# usir_board.net
KiCad netlist of a schematic drawn in EAGLE
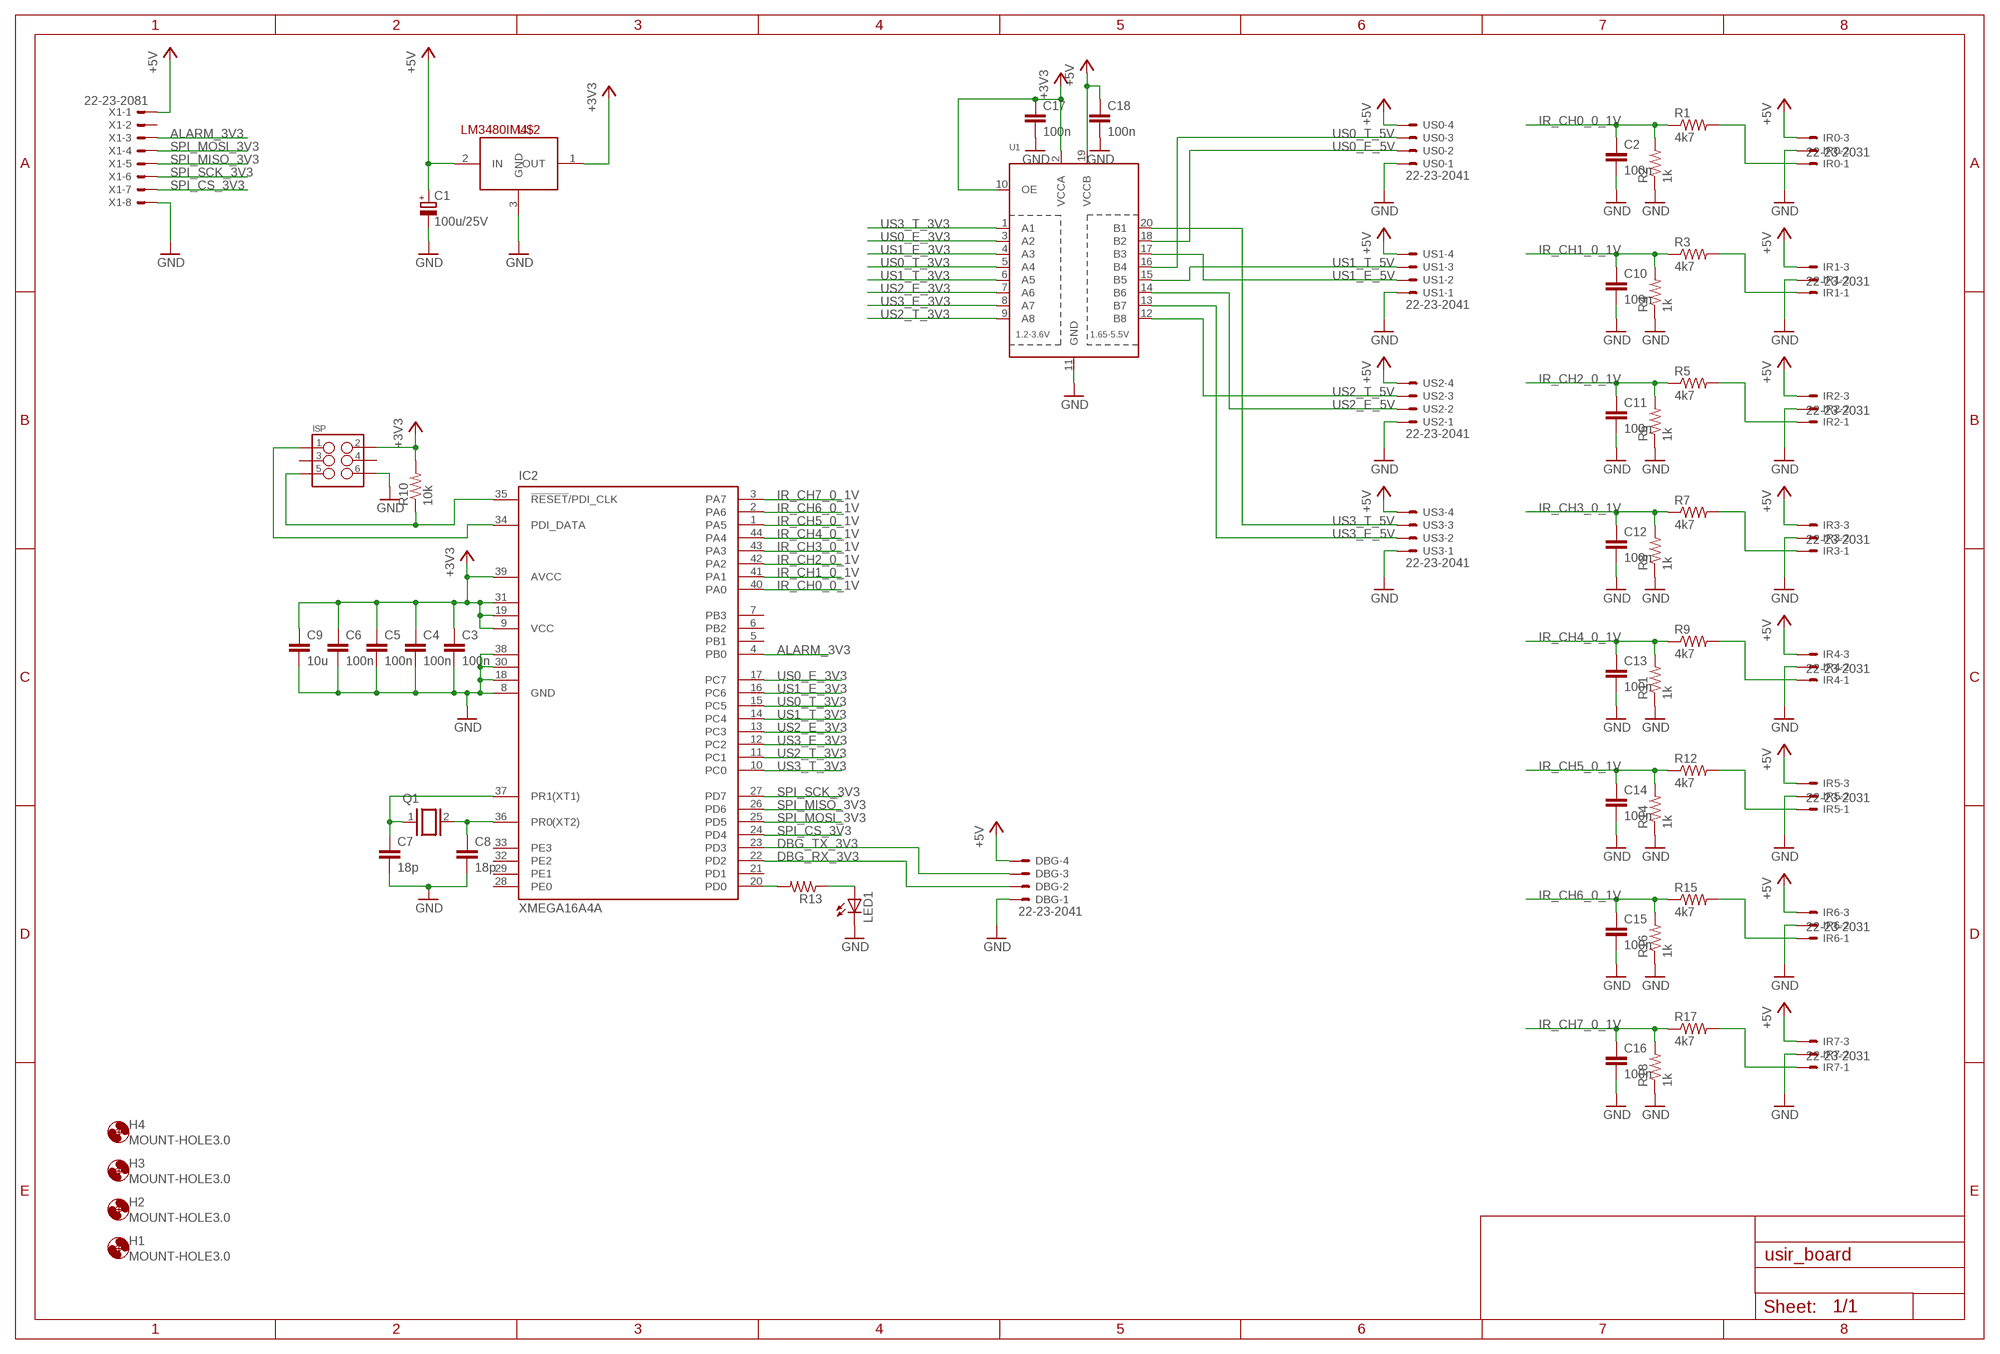
[diagram p0: schematic, sheet 1]

(export (version "E")
  (design (tool "Eeschema 10.0.6"))
  (components
    (comp (ref "C1")
      (value "100u/25V")
      (footprint "eagle-import:PANASONIC_E")
      (libsource (lib "eagle-import") (part "CPOL-EUE"))
    )
    (comp (ref "C2")
      (value "100n")
      (footprint "eagle-import:C0603")
      (libsource (lib "eagle-import") (part "C-EUC0603"))
    )
    (comp (ref "C3")
      (value "100n")
      (footprint "eagle-import:C0603")
      (libsource (lib "eagle-import") (part "C-EUC0603"))
    )
    (comp (ref "C4")
      (value "100n")
      (footprint "eagle-import:C0603")
      (libsource (lib "eagle-import") (part "C-EUC0603"))
    )
    (comp (ref "C5")
      (value "100n")
      (footprint "eagle-import:C0603")
      (libsource (lib "eagle-import") (part "C-EUC0603"))
    )
    (comp (ref "C6")
      (value "100n")
      (footprint "eagle-import:C0603")
      (libsource (lib "eagle-import") (part "C-EUC0603"))
    )
    (comp (ref "C7")
      (value "18p")
      (footprint "eagle-import:C0603")
      (libsource (lib "eagle-import") (part "C-EUC0603"))
    )
    (comp (ref "C8")
      (value "18p")
      (footprint "eagle-import:C0603")
      (libsource (lib "eagle-import") (part "C-EUC0603"))
    )
    (comp (ref "C9")
      (value "10u")
      (footprint "eagle-import:C0805")
      (libsource (lib "eagle-import") (part "C-EUC0805"))
    )
    (comp (ref "C10")
      (value "100n")
      (footprint "eagle-import:C0603")
      (libsource (lib "eagle-import") (part "C-EUC0603"))
    )
    (comp (ref "C11")
      (value "100n")
      (footprint "eagle-import:C0603")
      (libsource (lib "eagle-import") (part "C-EUC0603"))
    )
    (comp (ref "C12")
      (value "100n")
      (footprint "eagle-import:C0603")
      (libsource (lib "eagle-import") (part "C-EUC0603"))
    )
    (comp (ref "C13")
      (value "100n")
      (footprint "eagle-import:C0603")
      (libsource (lib "eagle-import") (part "C-EUC0603"))
    )
    (comp (ref "C14")
      (value "100n")
      (footprint "eagle-import:C0603")
      (libsource (lib "eagle-import") (part "C-EUC0603"))
    )
    (comp (ref "C15")
      (value "100n")
      (footprint "eagle-import:C0603")
      (libsource (lib "eagle-import") (part "C-EUC0603"))
    )
    (comp (ref "C16")
      (value "100n")
      (footprint "eagle-import:C0603")
      (libsource (lib "eagle-import") (part "C-EUC0603"))
    )
    (comp (ref "C17")
      (value "100n")
      (footprint "eagle-import:C0603")
      (libsource (lib "eagle-import") (part "C-EUC0603"))
    )
    (comp (ref "C18")
      (value "100n")
      (footprint "eagle-import:C0603")
      (libsource (lib "eagle-import") (part "C-EUC0603"))
    )
    (comp (ref "DBG")
      (value "22-23-2041")
      (footprint "eagle-import:22-23-2041")
      (fields (field (name "MF") "MOLEX"))
      (libsource (lib "eagle-import") (part "22-23-2041"))
    )
    (comp (ref "H1")
      (value "MOUNT-HOLE3.0")
      (footprint "eagle-import:3,0")
      (libsource (lib "eagle-import") (part "MOUNT-HOLE3.0"))
    )
    (comp (ref "H2")
      (value "MOUNT-HOLE3.0")
      (footprint "eagle-import:3,0")
      (libsource (lib "eagle-import") (part "MOUNT-HOLE3.0"))
    )
    (comp (ref "H3")
      (value "MOUNT-HOLE3.0")
      (footprint "eagle-import:3,0")
      (libsource (lib "eagle-import") (part "MOUNT-HOLE3.0"))
    )
    (comp (ref "H4")
      (value "MOUNT-HOLE3.0")
      (footprint "eagle-import:3,0")
      (libsource (lib "eagle-import") (part "MOUNT-HOLE3.0"))
    )
    (comp (ref "IC2")
      (value "XMEGA16A4A")
      (footprint "eagle-import:TQFP44")
      (libsource (lib "eagle-import") (part "XMEGA16A4A"))
    )
    (comp (ref "IR0")
      (value "22-23-2031")
      (footprint "eagle-import:22-23-2031")
      (fields (field (name "MF") "MOLEX"))
      (libsource (lib "eagle-import") (part "22-23-2031"))
    )
    (comp (ref "IR1")
      (value "22-23-2031")
      (footprint "eagle-import:22-23-2031")
      (fields (field (name "MF") "MOLEX"))
      (libsource (lib "eagle-import") (part "22-23-2031"))
    )
    (comp (ref "IR2")
      (value "22-23-2031")
      (footprint "eagle-import:22-23-2031")
      (fields (field (name "MF") "MOLEX"))
      (libsource (lib "eagle-import") (part "22-23-2031"))
    )
    (comp (ref "IR3")
      (value "22-23-2031")
      (footprint "eagle-import:22-23-2031")
      (fields (field (name "MF") "MOLEX"))
      (libsource (lib "eagle-import") (part "22-23-2031"))
    )
    (comp (ref "IR4")
      (value "22-23-2031")
      (footprint "eagle-import:22-23-2031")
      (fields (field (name "MF") "MOLEX"))
      (libsource (lib "eagle-import") (part "22-23-2031"))
    )
    (comp (ref "IR5")
      (value "22-23-2031")
      (footprint "eagle-import:22-23-2031")
      (fields (field (name "MF") "MOLEX"))
      (libsource (lib "eagle-import") (part "22-23-2031"))
    )
    (comp (ref "IR6")
      (value "22-23-2031")
      (footprint "eagle-import:22-23-2031")
      (fields (field (name "MF") "MOLEX"))
      (libsource (lib "eagle-import") (part "22-23-2031"))
    )
    (comp (ref "IR7")
      (value "22-23-2031")
      (footprint "eagle-import:22-23-2031")
      (fields (field (name "MF") "MOLEX"))
      (libsource (lib "eagle-import") (part "22-23-2031"))
    )
    (comp (ref "ISP")
      (value "M03X2POGO_PINS")
      (footprint "eagle-import:2X3_POGO")
      (libsource (lib "eagle-import") (part "M03X2POGO_PINS"))
    )
    (comp (ref "LED1")
      (value "LEDCHIP-LED0603")
      (footprint "eagle-import:CHIP-LED0603")
      (libsource (lib "eagle-import") (part "LEDCHIP-LED0603"))
    )
    (comp (ref "Q1")
      (value "XTAL/S")
      (footprint "eagle-import:QS")
      (libsource (lib "eagle-import") (part "XTAL/S"))
    )
    (comp (ref "R1")
      (value "4k7")
      (footprint "eagle-import:R0603")
      (libsource (lib "eagle-import") (part "R-US_R0603"))
    )
    (comp (ref "R2")
      (value "1k")
      (footprint "eagle-import:R0603")
      (libsource (lib "eagle-import") (part "R-US_R0603"))
    )
    (comp (ref "R3")
      (value "4k7")
      (footprint "eagle-import:R0603")
      (libsource (lib "eagle-import") (part "R-US_R0603"))
    )
    (comp (ref "R4")
      (value "1k")
      (footprint "eagle-import:R0603")
      (libsource (lib "eagle-import") (part "R-US_R0603"))
    )
    (comp (ref "R5")
      (value "4k7")
      (footprint "eagle-import:R0603")
      (libsource (lib "eagle-import") (part "R-US_R0603"))
    )
    (comp (ref "R6")
      (value "1k")
      (footprint "eagle-import:R0603")
      (libsource (lib "eagle-import") (part "R-US_R0603"))
    )
    (comp (ref "R7")
      (value "4k7")
      (footprint "eagle-import:R0603")
      (libsource (lib "eagle-import") (part "R-US_R0603"))
    )
    (comp (ref "R8")
      (value "1k")
      (footprint "eagle-import:R0603")
      (libsource (lib "eagle-import") (part "R-US_R0603"))
    )
    (comp (ref "R9")
      (value "4k7")
      (footprint "eagle-import:R0603")
      (libsource (lib "eagle-import") (part "R-US_R0603"))
    )
    (comp (ref "R10")
      (value "10k")
      (footprint "eagle-import:R0603")
      (libsource (lib "eagle-import") (part "R-US_R0603"))
    )
    (comp (ref "R11")
      (value "1k")
      (footprint "eagle-import:R0603")
      (libsource (lib "eagle-import") (part "R-US_R0603"))
    )
    (comp (ref "R12")
      (value "4k7")
      (footprint "eagle-import:R0603")
      (libsource (lib "eagle-import") (part "R-US_R0603"))
    )
    (comp (ref "R13")
      (value "R-US_R0603")
      (footprint "eagle-import:R0603")
      (libsource (lib "eagle-import") (part "R-US_R0603"))
    )
    (comp (ref "R14")
      (value "1k")
      (footprint "eagle-import:R0603")
      (libsource (lib "eagle-import") (part "R-US_R0603"))
    )
    (comp (ref "R15")
      (value "4k7")
      (footprint "eagle-import:R0603")
      (libsource (lib "eagle-import") (part "R-US_R0603"))
    )
    (comp (ref "R16")
      (value "1k")
      (footprint "eagle-import:R0603")
      (libsource (lib "eagle-import") (part "R-US_R0603"))
    )
    (comp (ref "R17")
      (value "4k7")
      (footprint "eagle-import:R0603")
      (libsource (lib "eagle-import") (part "R-US_R0603"))
    )
    (comp (ref "R18")
      (value "1k")
      (footprint "eagle-import:R0603")
      (libsource (lib "eagle-import") (part "R-US_R0603"))
    )
    (comp (ref "U$2")
      (value "LM3480IM4")
      (footprint "eagle-import:SOT23-3")
      (libsource (lib "eagle-import") (part "LM3480IM4"))
    )
    (comp (ref "U1")
      (value "TXB0108PWR")
      (footprint "eagle-import:TSSOP20")
      (libsource (lib "eagle-import") (part "TXB0108PWR"))
    )
    (comp (ref "US0")
      (value "22-23-2041")
      (footprint "eagle-import:22-23-2041")
      (fields (field (name "MF") "MOLEX"))
      (libsource (lib "eagle-import") (part "22-23-2041"))
    )
    (comp (ref "US1")
      (value "22-23-2041")
      (footprint "eagle-import:22-23-2041")
      (fields (field (name "MF") "MOLEX"))
      (libsource (lib "eagle-import") (part "22-23-2041"))
    )
    (comp (ref "US2")
      (value "22-23-2041")
      (footprint "eagle-import:22-23-2041")
      (fields (field (name "MF") "MOLEX"))
      (libsource (lib "eagle-import") (part "22-23-2041"))
    )
    (comp (ref "US3")
      (value "22-23-2041")
      (footprint "eagle-import:22-23-2041")
      (fields (field (name "MF") "MOLEX"))
      (libsource (lib "eagle-import") (part "22-23-2041"))
    )
    (comp (ref "X1")
      (value "22-23-2081")
      (footprint "eagle-import:22-23-2081")
      (fields (field (name "MF") "MOLEX"))
      (libsource (lib "eagle-import") (part "22-23-2081"))
    )
  )
  (nets
    (net (code "1") (name "+3V3") (class "Default")
      (node (ref "C17") (pin "1") (pinfunction "1_1") (pintype "passive"))
      (node (ref "C3") (pin "1") (pinfunction "1_1") (pintype "passive"))
      (node (ref "C4") (pin "1") (pinfunction "1_1") (pintype "passive"))
      (node (ref "C5") (pin "1") (pinfunction "1_1") (pintype "passive"))
      (node (ref "C6") (pin "1") (pinfunction "1_1") (pintype "passive"))
      (node (ref "C9") (pin "1") (pinfunction "1_1") (pintype "passive"))
      (node (ref "IC2") (pin "19") (pinfunction "VCC1_19") (pintype "power_in"))
      (node (ref "IC2") (pin "31") (pinfunction "VCC2_31") (pintype "power_in"))
      (node (ref "IC2") (pin "39") (pinfunction "AVCC_39") (pintype "power_in"))
      (node (ref "IC2") (pin "9") (pinfunction "VCC_9") (pintype "power_in"))
      (node (ref "ISP") (pin "P$2") (pinfunction "2_P$2") (pintype "bidirectional"))
      (node (ref "R10") (pin "2") (pinfunction "2_2") (pintype "passive"))
      (node (ref "U$2") (pin "1") (pinfunction "OUT_1") (pintype "bidirectional"))
      (node (ref "U1") (pin "10") (pinfunction "OE_10") (pintype "bidirectional"))
      (node (ref "U1") (pin "2") (pinfunction "VCCA_2") (pintype "bidirectional"))
    )
    (net (code "2") (name "+5V") (class "Default")
      (node (ref "C1") (pin "+") (pinfunction "+_+") (pintype "passive"))
      (node (ref "C18") (pin "1") (pinfunction "1_1") (pintype "passive"))
      (node (ref "DBG") (pin "4") (pinfunction "S_4") (pintype "passive"))
      (node (ref "IR0") (pin "3") (pinfunction "S_3") (pintype "passive"))
      (node (ref "IR1") (pin "3") (pinfunction "S_3") (pintype "passive"))
      (node (ref "IR2") (pin "3") (pinfunction "S_3") (pintype "passive"))
      (node (ref "IR3") (pin "3") (pinfunction "S_3") (pintype "passive"))
      (node (ref "IR4") (pin "3") (pinfunction "S_3") (pintype "passive"))
      (node (ref "IR5") (pin "3") (pinfunction "S_3") (pintype "passive"))
      (node (ref "IR6") (pin "3") (pinfunction "S_3") (pintype "passive"))
      (node (ref "IR7") (pin "3") (pinfunction "S_3") (pintype "passive"))
      (node (ref "U$2") (pin "2") (pinfunction "IN_2") (pintype "bidirectional"))
      (node (ref "U1") (pin "19") (pinfunction "VCCB_19") (pintype "bidirectional"))
      (node (ref "US0") (pin "4") (pinfunction "S_4") (pintype "passive"))
      (node (ref "US1") (pin "4") (pinfunction "S_4") (pintype "passive"))
      (node (ref "US2") (pin "4") (pinfunction "S_4") (pintype "passive"))
      (node (ref "US3") (pin "4") (pinfunction "S_4") (pintype "passive"))
      (node (ref "X1") (pin "1") (pinfunction "S_1") (pintype "passive"))
    )
    (net (code "3") (name "/ALARM_3V3") (class "Default")
      (node (ref "IC2") (pin "4") (pinfunction "PB0_4") (pintype "bidirectional"))
      (node (ref "X1") (pin "3") (pinfunction "S_3") (pintype "passive"))
    )
    (net (code "4") (name "/DBG_RX_3V3") (class "Default")
      (node (ref "DBG") (pin "2") (pinfunction "S_2") (pintype "passive"))
      (node (ref "IC2") (pin "22") (pinfunction "PD2_22") (pintype "bidirectional"))
    )
    (net (code "5") (name "/DBG_TX_3V3") (class "Default")
      (node (ref "DBG") (pin "3") (pinfunction "S_3") (pintype "passive"))
      (node (ref "IC2") (pin "23") (pinfunction "PD3_23") (pintype "bidirectional"))
    )
    (net (code "6") (name "/IR_CH0_0_1V") (class "Default")
      (node (ref "C2") (pin "1") (pinfunction "1_1") (pintype "passive"))
      (node (ref "IC2") (pin "40") (pinfunction "PA0_40") (pintype "bidirectional"))
      (node (ref "R1") (pin "1") (pinfunction "1_1") (pintype "passive"))
      (node (ref "R2") (pin "2") (pinfunction "2_2") (pintype "passive"))
    )
    (net (code "7") (name "/IR_CH1_0_1V") (class "Default")
      (node (ref "C10") (pin "1") (pinfunction "1_1") (pintype "passive"))
      (node (ref "IC2") (pin "41") (pinfunction "PA1_41") (pintype "bidirectional"))
      (node (ref "R3") (pin "1") (pinfunction "1_1") (pintype "passive"))
      (node (ref "R4") (pin "2") (pinfunction "2_2") (pintype "passive"))
    )
    (net (code "8") (name "/IR_CH2_0_1V") (class "Default")
      (node (ref "C11") (pin "1") (pinfunction "1_1") (pintype "passive"))
      (node (ref "IC2") (pin "42") (pinfunction "PA2_42") (pintype "bidirectional"))
      (node (ref "R5") (pin "1") (pinfunction "1_1") (pintype "passive"))
      (node (ref "R6") (pin "2") (pinfunction "2_2") (pintype "passive"))
    )
    (net (code "9") (name "/IR_CH3_0_1V") (class "Default")
      (node (ref "C12") (pin "1") (pinfunction "1_1") (pintype "passive"))
      (node (ref "IC2") (pin "43") (pinfunction "PA3_43") (pintype "bidirectional"))
      (node (ref "R7") (pin "1") (pinfunction "1_1") (pintype "passive"))
      (node (ref "R8") (pin "2") (pinfunction "2_2") (pintype "passive"))
    )
    (net (code "10") (name "/IR_CH4_0_1V") (class "Default")
      (node (ref "C13") (pin "1") (pinfunction "1_1") (pintype "passive"))
      (node (ref "IC2") (pin "44") (pinfunction "PA4_44") (pintype "bidirectional"))
      (node (ref "R11") (pin "2") (pinfunction "2_2") (pintype "passive"))
      (node (ref "R9") (pin "1") (pinfunction "1_1") (pintype "passive"))
    )
    (net (code "11") (name "/IR_CH5_0_1V") (class "Default")
      (node (ref "C14") (pin "1") (pinfunction "1_1") (pintype "passive"))
      (node (ref "IC2") (pin "1") (pinfunction "PA5_1") (pintype "bidirectional"))
      (node (ref "R12") (pin "1") (pinfunction "1_1") (pintype "passive"))
      (node (ref "R14") (pin "2") (pinfunction "2_2") (pintype "passive"))
    )
    (net (code "12") (name "/IR_CH6_0_1V") (class "Default")
      (node (ref "C15") (pin "1") (pinfunction "1_1") (pintype "passive"))
      (node (ref "IC2") (pin "2") (pinfunction "PA6_2") (pintype "bidirectional"))
      (node (ref "R15") (pin "1") (pinfunction "1_1") (pintype "passive"))
      (node (ref "R16") (pin "2") (pinfunction "2_2") (pintype "passive"))
    )
    (net (code "13") (name "/IR_CH7_0_1V") (class "Default")
      (node (ref "C16") (pin "1") (pinfunction "1_1") (pintype "passive"))
      (node (ref "IC2") (pin "3") (pinfunction "PA7_3") (pintype "bidirectional"))
      (node (ref "R17") (pin "1") (pinfunction "1_1") (pintype "passive"))
      (node (ref "R18") (pin "2") (pinfunction "2_2") (pintype "passive"))
    )
    (net (code "14") (name "/SPI_CS_3V3") (class "Default")
      (node (ref "IC2") (pin "24") (pinfunction "PD4_24") (pintype "bidirectional"))
      (node (ref "X1") (pin "7") (pinfunction "S_7") (pintype "passive"))
    )
    (net (code "15") (name "/SPI_MISO_3V3") (class "Default")
      (node (ref "IC2") (pin "26") (pinfunction "PD6_26") (pintype "bidirectional"))
      (node (ref "X1") (pin "5") (pinfunction "S_5") (pintype "passive"))
    )
    (net (code "16") (name "/SPI_MOSI_3V3") (class "Default")
      (node (ref "IC2") (pin "25") (pinfunction "PD5_25") (pintype "bidirectional"))
      (node (ref "X1") (pin "4") (pinfunction "S_4") (pintype "passive"))
    )
    (net (code "17") (name "/SPI_SCK_3V3") (class "Default")
      (node (ref "IC2") (pin "27") (pinfunction "PD7_27") (pintype "bidirectional"))
      (node (ref "X1") (pin "6") (pinfunction "S_6") (pintype "passive"))
    )
    (net (code "18") (name "/US0_E_3V3") (class "Default")
      (node (ref "IC2") (pin "17") (pinfunction "PC7_17") (pintype "bidirectional"))
      (node (ref "U1") (pin "3") (pinfunction "A2_3") (pintype "bidirectional"))
    )
    (net (code "19") (name "/US0_E_5V") (class "Default")
      (node (ref "U1") (pin "18") (pinfunction "B2_18") (pintype "bidirectional"))
      (node (ref "US0") (pin "2") (pinfunction "S_2") (pintype "passive"))
    )
    (net (code "20") (name "/US0_T_3V3") (class "Default")
      (node (ref "IC2") (pin "15") (pinfunction "PC5_15") (pintype "bidirectional"))
      (node (ref "U1") (pin "5") (pinfunction "A4_5") (pintype "bidirectional"))
    )
    (net (code "21") (name "/US0_T_5V") (class "Default")
      (node (ref "U1") (pin "16") (pinfunction "B4_16") (pintype "bidirectional"))
      (node (ref "US0") (pin "3") (pinfunction "S_3") (pintype "passive"))
    )
    (net (code "22") (name "/US1_E_3V3") (class "Default")
      (node (ref "IC2") (pin "16") (pinfunction "PC6_16") (pintype "bidirectional"))
      (node (ref "U1") (pin "4") (pinfunction "A3_4") (pintype "bidirectional"))
    )
    (net (code "23") (name "/US1_E_5V") (class "Default")
      (node (ref "U1") (pin "17") (pinfunction "B3_17") (pintype "bidirectional"))
      (node (ref "US1") (pin "2") (pinfunction "S_2") (pintype "passive"))
    )
    (net (code "24") (name "/US1_T_3V3") (class "Default")
      (node (ref "IC2") (pin "14") (pinfunction "PC4_14") (pintype "bidirectional"))
      (node (ref "U1") (pin "6") (pinfunction "A5_6") (pintype "bidirectional"))
    )
    (net (code "25") (name "/US1_T_5V") (class "Default")
      (node (ref "U1") (pin "15") (pinfunction "B5_15") (pintype "bidirectional"))
      (node (ref "US1") (pin "3") (pinfunction "S_3") (pintype "passive"))
    )
    (net (code "26") (name "/US2_E_3V3") (class "Default")
      (node (ref "IC2") (pin "13") (pinfunction "PC3_13") (pintype "bidirectional"))
      (node (ref "U1") (pin "7") (pinfunction "A6_7") (pintype "bidirectional"))
    )
    (net (code "27") (name "/US2_E_5V") (class "Default")
      (node (ref "U1") (pin "14") (pinfunction "B6_14") (pintype "bidirectional"))
      (node (ref "US2") (pin "2") (pinfunction "S_2") (pintype "passive"))
    )
    (net (code "28") (name "/US2_T_3V3") (class "Default")
      (node (ref "IC2") (pin "11") (pinfunction "PC1_11") (pintype "bidirectional"))
      (node (ref "U1") (pin "9") (pinfunction "A8_9") (pintype "bidirectional"))
    )
    (net (code "29") (name "/US2_T_5V") (class "Default")
      (node (ref "U1") (pin "12") (pinfunction "B8_12") (pintype "bidirectional"))
      (node (ref "US2") (pin "3") (pinfunction "S_3") (pintype "passive"))
    )
    (net (code "30") (name "/US3_E_3V3") (class "Default")
      (node (ref "IC2") (pin "12") (pinfunction "PC2_12") (pintype "bidirectional"))
      (node (ref "U1") (pin "8") (pinfunction "A7_8") (pintype "bidirectional"))
    )
    (net (code "31") (name "/US3_E_5V") (class "Default")
      (node (ref "U1") (pin "13") (pinfunction "B7_13") (pintype "bidirectional"))
      (node (ref "US3") (pin "2") (pinfunction "S_2") (pintype "passive"))
    )
    (net (code "32") (name "/US3_T_3V3") (class "Default")
      (node (ref "IC2") (pin "10") (pinfunction "PC0_10") (pintype "bidirectional"))
      (node (ref "U1") (pin "1") (pinfunction "A1_1") (pintype "bidirectional"))
    )
    (net (code "33") (name "/US3_T_5V") (class "Default")
      (node (ref "U1") (pin "20") (pinfunction "B1_20") (pintype "bidirectional"))
      (node (ref "US3") (pin "3") (pinfunction "S_3") (pintype "passive"))
    )
    (net (code "34") (name "GND") (class "Default")
      (node (ref "C1") (pin "-") (pinfunction "-_-") (pintype "passive"))
      (node (ref "C10") (pin "2") (pinfunction "2_2") (pintype "passive"))
      (node (ref "C11") (pin "2") (pinfunction "2_2") (pintype "passive"))
      (node (ref "C12") (pin "2") (pinfunction "2_2") (pintype "passive"))
      (node (ref "C13") (pin "2") (pinfunction "2_2") (pintype "passive"))
      (node (ref "C14") (pin "2") (pinfunction "2_2") (pintype "passive"))
      (node (ref "C15") (pin "2") (pinfunction "2_2") (pintype "passive"))
      (node (ref "C16") (pin "2") (pinfunction "2_2") (pintype "passive"))
      (node (ref "C17") (pin "2") (pinfunction "2_2") (pintype "passive"))
      (node (ref "C18") (pin "2") (pinfunction "2_2") (pintype "passive"))
      (node (ref "C2") (pin "2") (pinfunction "2_2") (pintype "passive"))
      (node (ref "C3") (pin "2") (pinfunction "2_2") (pintype "passive"))
      (node (ref "C4") (pin "2") (pinfunction "2_2") (pintype "passive"))
      (node (ref "C5") (pin "2") (pinfunction "2_2") (pintype "passive"))
      (node (ref "C6") (pin "2") (pinfunction "2_2") (pintype "passive"))
      (node (ref "C7") (pin "2") (pinfunction "2_2") (pintype "passive"))
      (node (ref "C8") (pin "2") (pinfunction "2_2") (pintype "passive"))
      (node (ref "C9") (pin "2") (pinfunction "2_2") (pintype "passive"))
      (node (ref "DBG") (pin "1") (pinfunction "S_1") (pintype "passive"))
      (node (ref "IC2") (pin "18") (pinfunction "GND1_18") (pintype "power_in"))
      (node (ref "IC2") (pin "30") (pinfunction "GND2_30") (pintype "power_in"))
      (node (ref "IC2") (pin "38") (pinfunction "GND3_38") (pintype "power_in"))
      (node (ref "IC2") (pin "8") (pinfunction "GND_8") (pintype "power_in"))
      (node (ref "IR0") (pin "2") (pinfunction "S_2") (pintype "passive"))
      (node (ref "IR1") (pin "2") (pinfunction "S_2") (pintype "passive"))
      (node (ref "IR2") (pin "2") (pinfunction "S_2") (pintype "passive"))
      (node (ref "IR3") (pin "2") (pinfunction "S_2") (pintype "passive"))
      (node (ref "IR4") (pin "2") (pinfunction "S_2") (pintype "passive"))
      (node (ref "IR5") (pin "2") (pinfunction "S_2") (pintype "passive"))
      (node (ref "IR6") (pin "2") (pinfunction "S_2") (pintype "passive"))
      (node (ref "IR7") (pin "2") (pinfunction "S_2") (pintype "passive"))
      (node (ref "ISP") (pin "P$6") (pinfunction "6_P$6") (pintype "bidirectional"))
      (node (ref "LED1") (pin "C") (pinfunction "C_C") (pintype "passive"))
      (node (ref "R11") (pin "1") (pinfunction "1_1") (pintype "passive"))
      (node (ref "R14") (pin "1") (pinfunction "1_1") (pintype "passive"))
      (node (ref "R16") (pin "1") (pinfunction "1_1") (pintype "passive"))
      (node (ref "R18") (pin "1") (pinfunction "1_1") (pintype "passive"))
      (node (ref "R2") (pin "1") (pinfunction "1_1") (pintype "passive"))
      (node (ref "R4") (pin "1") (pinfunction "1_1") (pintype "passive"))
      (node (ref "R6") (pin "1") (pinfunction "1_1") (pintype "passive"))
      (node (ref "R8") (pin "1") (pinfunction "1_1") (pintype "passive"))
      (node (ref "U$2") (pin "3") (pinfunction "GND_3") (pintype "bidirectional"))
      (node (ref "U1") (pin "11") (pinfunction "GND_11") (pintype "bidirectional"))
      (node (ref "US0") (pin "1") (pinfunction "S_1") (pintype "passive"))
      (node (ref "US1") (pin "1") (pinfunction "S_1") (pintype "passive"))
      (node (ref "US2") (pin "1") (pinfunction "S_1") (pintype "passive"))
      (node (ref "US3") (pin "1") (pinfunction "S_1") (pintype "passive"))
      (node (ref "X1") (pin "8") (pinfunction "S_8") (pintype "passive"))
    )
    (net (code "35") (name "Net-(IC2-PD0)") (class "Default")
      (node (ref "IC2") (pin "20") (pinfunction "PD0_20") (pintype "bidirectional"))
      (node (ref "R13") (pin "2") (pinfunction "2_2") (pintype "passive"))
    )
    (net (code "36") (name "Net-(IC2-PDI_DATA)") (class "Default")
      (node (ref "IC2") (pin "34") (pinfunction "PDI_DATA_34") (pintype "bidirectional"))
      (node (ref "ISP") (pin "P$1") (pinfunction "1_P$1") (pintype "bidirectional"))
    )
    (net (code "37") (name "Net-(IC2-PR0(XT2))") (class "Default")
      (node (ref "C8") (pin "1") (pinfunction "1_1") (pintype "passive"))
      (node (ref "IC2") (pin "36") (pinfunction "PR0(XT2)_36") (pintype "bidirectional"))
      (node (ref "Q1") (pin "2") (pinfunction "2_2") (pintype "passive"))
    )
    (net (code "38") (name "Net-(IC2-PR1(XT1))") (class "Default")
      (node (ref "C7") (pin "1") (pinfunction "1_1") (pintype "passive"))
      (node (ref "IC2") (pin "37") (pinfunction "PR1(XT1)_37") (pintype "bidirectional"))
      (node (ref "Q1") (pin "1") (pinfunction "1_1") (pintype "passive"))
    )
    (net (code "39") (name "Net-(IC2-~{RESET}{slash}PDI_CLK)") (class "Default")
      (node (ref "IC2") (pin "35") (pinfunction "~{RESET}/PDI_CLK_35") (pintype "bidirectional"))
      (node (ref "ISP") (pin "P$5") (pinfunction "5_P$5") (pintype "bidirectional"))
      (node (ref "R10") (pin "1") (pinfunction "1_1") (pintype "passive"))
    )
    (net (code "40") (name "Net-(IR0A-S)") (class "Default")
      (node (ref "IR0") (pin "1") (pinfunction "S_1") (pintype "passive"))
      (node (ref "R1") (pin "2") (pinfunction "2_2") (pintype "passive"))
    )
    (net (code "41") (name "Net-(IR1A-S)") (class "Default")
      (node (ref "IR1") (pin "1") (pinfunction "S_1") (pintype "passive"))
      (node (ref "R3") (pin "2") (pinfunction "2_2") (pintype "passive"))
    )
    (net (code "42") (name "Net-(IR2A-S)") (class "Default")
      (node (ref "IR2") (pin "1") (pinfunction "S_1") (pintype "passive"))
      (node (ref "R5") (pin "2") (pinfunction "2_2") (pintype "passive"))
    )
    (net (code "43") (name "Net-(IR3A-S)") (class "Default")
      (node (ref "IR3") (pin "1") (pinfunction "S_1") (pintype "passive"))
      (node (ref "R7") (pin "2") (pinfunction "2_2") (pintype "passive"))
    )
    (net (code "44") (name "Net-(IR4A-S)") (class "Default")
      (node (ref "IR4") (pin "1") (pinfunction "S_1") (pintype "passive"))
      (node (ref "R9") (pin "2") (pinfunction "2_2") (pintype "passive"))
    )
    (net (code "45") (name "Net-(IR5A-S)") (class "Default")
      (node (ref "IR5") (pin "1") (pinfunction "S_1") (pintype "passive"))
      (node (ref "R12") (pin "2") (pinfunction "2_2") (pintype "passive"))
    )
    (net (code "46") (name "Net-(IR6A-S)") (class "Default")
      (node (ref "IR6") (pin "1") (pinfunction "S_1") (pintype "passive"))
      (node (ref "R15") (pin "2") (pinfunction "2_2") (pintype "passive"))
    )
    (net (code "47") (name "Net-(IR7A-S)") (class "Default")
      (node (ref "IR7") (pin "1") (pinfunction "S_1") (pintype "passive"))
      (node (ref "R17") (pin "2") (pinfunction "2_2") (pintype "passive"))
    )
    (net (code "48") (name "Net-(LED1-PadA)") (class "Default")
      (node (ref "LED1") (pin "A") (pinfunction "A_A") (pintype "passive"))
      (node (ref "R13") (pin "1") (pinfunction "1_1") (pintype "passive"))
    )
    (net (code "49") (name "unconnected-(IC2-PB1-Pad5)") (class "Default")
      (node (ref "IC2") (pin "5") (pinfunction "PB1_5") (pintype "bidirectional"))
    )
    (net (code "50") (name "unconnected-(IC2-PB2-Pad6)") (class "Default")
      (node (ref "IC2") (pin "6") (pinfunction "PB2_6") (pintype "bidirectional"))
    )
    (net (code "51") (name "unconnected-(IC2-PB3-Pad7)") (class "Default")
      (node (ref "IC2") (pin "7") (pinfunction "PB3_7") (pintype "bidirectional"))
    )
    (net (code "52") (name "unconnected-(IC2-PD1-Pad21)") (class "Default")
      (node (ref "IC2") (pin "21") (pinfunction "PD1_21") (pintype "bidirectional"))
    )
    (net (code "53") (name "unconnected-(IC2-PE0-Pad28)") (class "Default")
      (node (ref "IC2") (pin "28") (pinfunction "PE0_28") (pintype "bidirectional"))
    )
    (net (code "54") (name "unconnected-(IC2-PE1-Pad29)") (class "Default")
      (node (ref "IC2") (pin "29") (pinfunction "PE1_29") (pintype "bidirectional"))
    )
    (net (code "55") (name "unconnected-(IC2-PE2-Pad32)") (class "Default")
      (node (ref "IC2") (pin "32") (pinfunction "PE2_32") (pintype "bidirectional"))
    )
    (net (code "56") (name "unconnected-(IC2-PE3-Pad33)") (class "Default")
      (node (ref "IC2") (pin "33") (pinfunction "PE3_33") (pintype "bidirectional"))
    )
    (net (code "57") (name "unconnected-(ISP-3-PadP$3)") (class "Default")
      (node (ref "ISP") (pin "P$3") (pinfunction "3_P$3") (pintype "bidirectional"))
    )
    (net (code "58") (name "unconnected-(ISP-4-PadP$4)") (class "Default")
      (node (ref "ISP") (pin "P$4") (pinfunction "4_P$4") (pintype "bidirectional"))
    )
    (net (code "59") (name "unconnected-(X1B-S-Pad2)") (class "Default")
      (node (ref "X1") (pin "2") (pinfunction "S_2") (pintype "passive"))
    )
  )
)
